# Puzzle_Controller.net
KiCad netlist of a schematic drawn in EAGLE
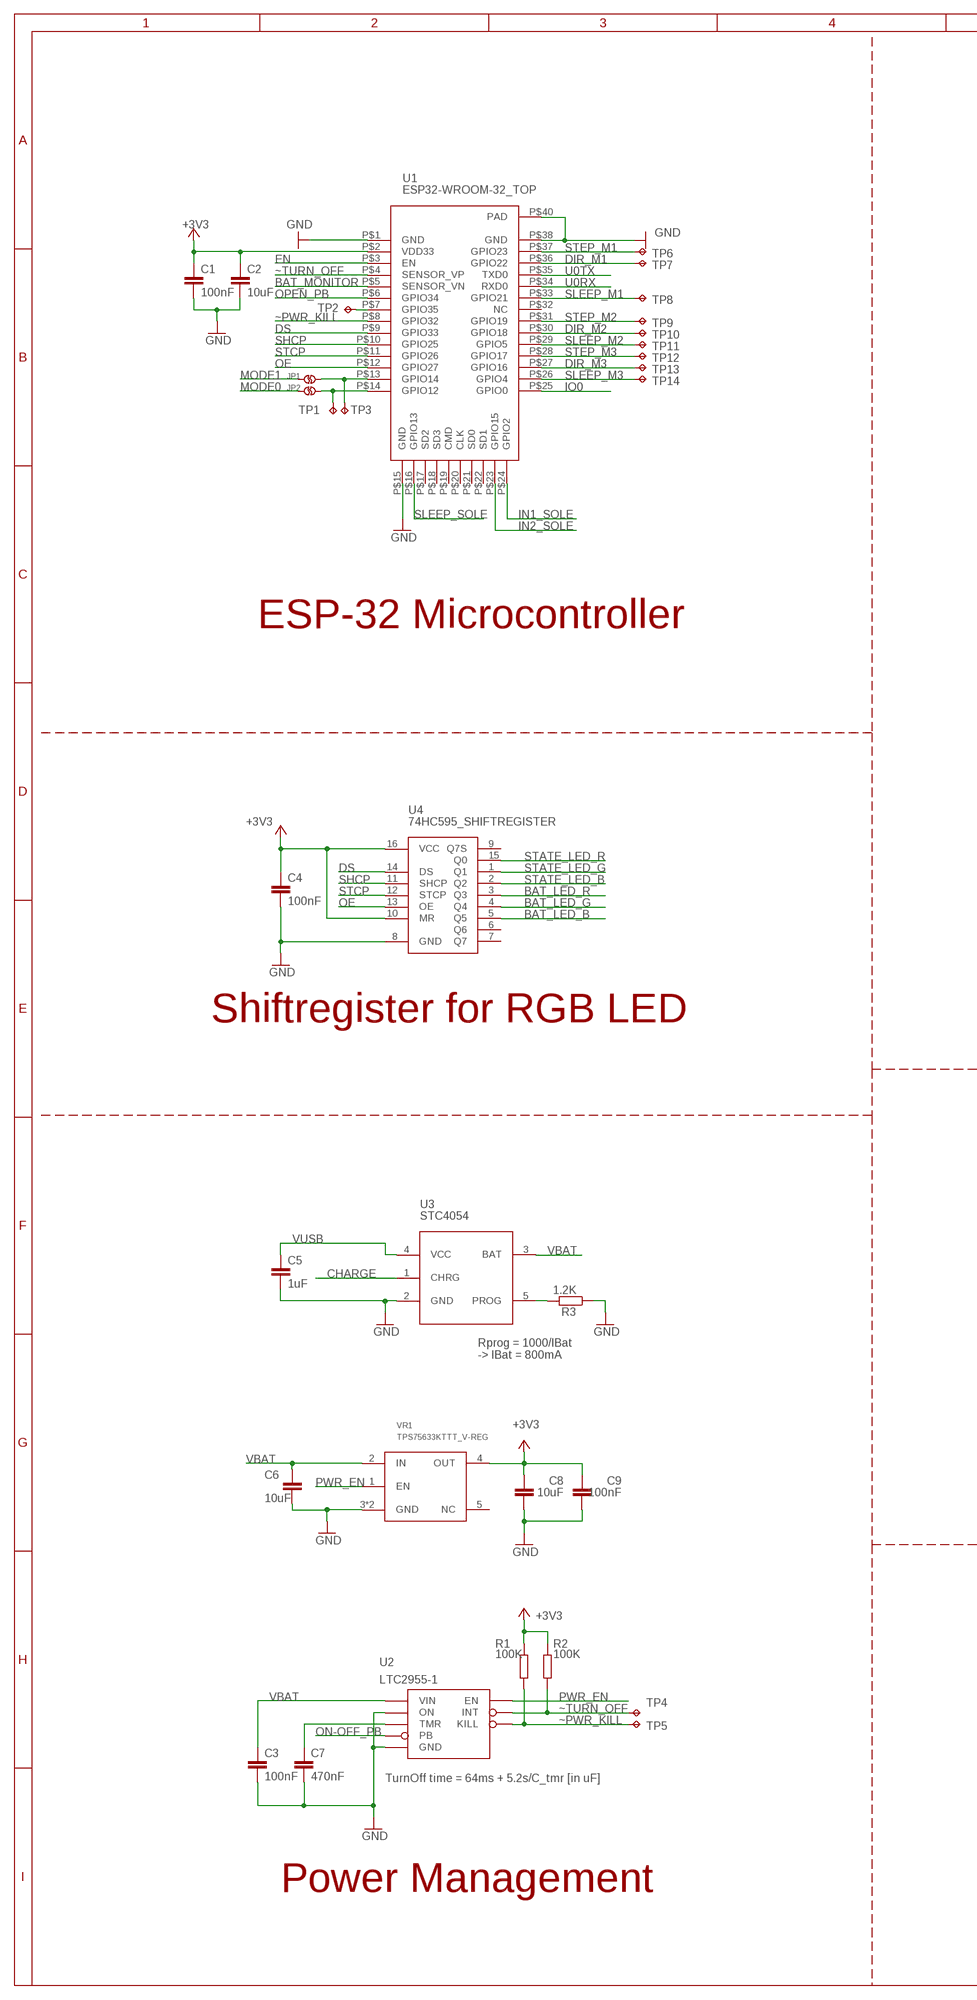
[diagram p0: schematic, sheet 1, part 1 of 2]
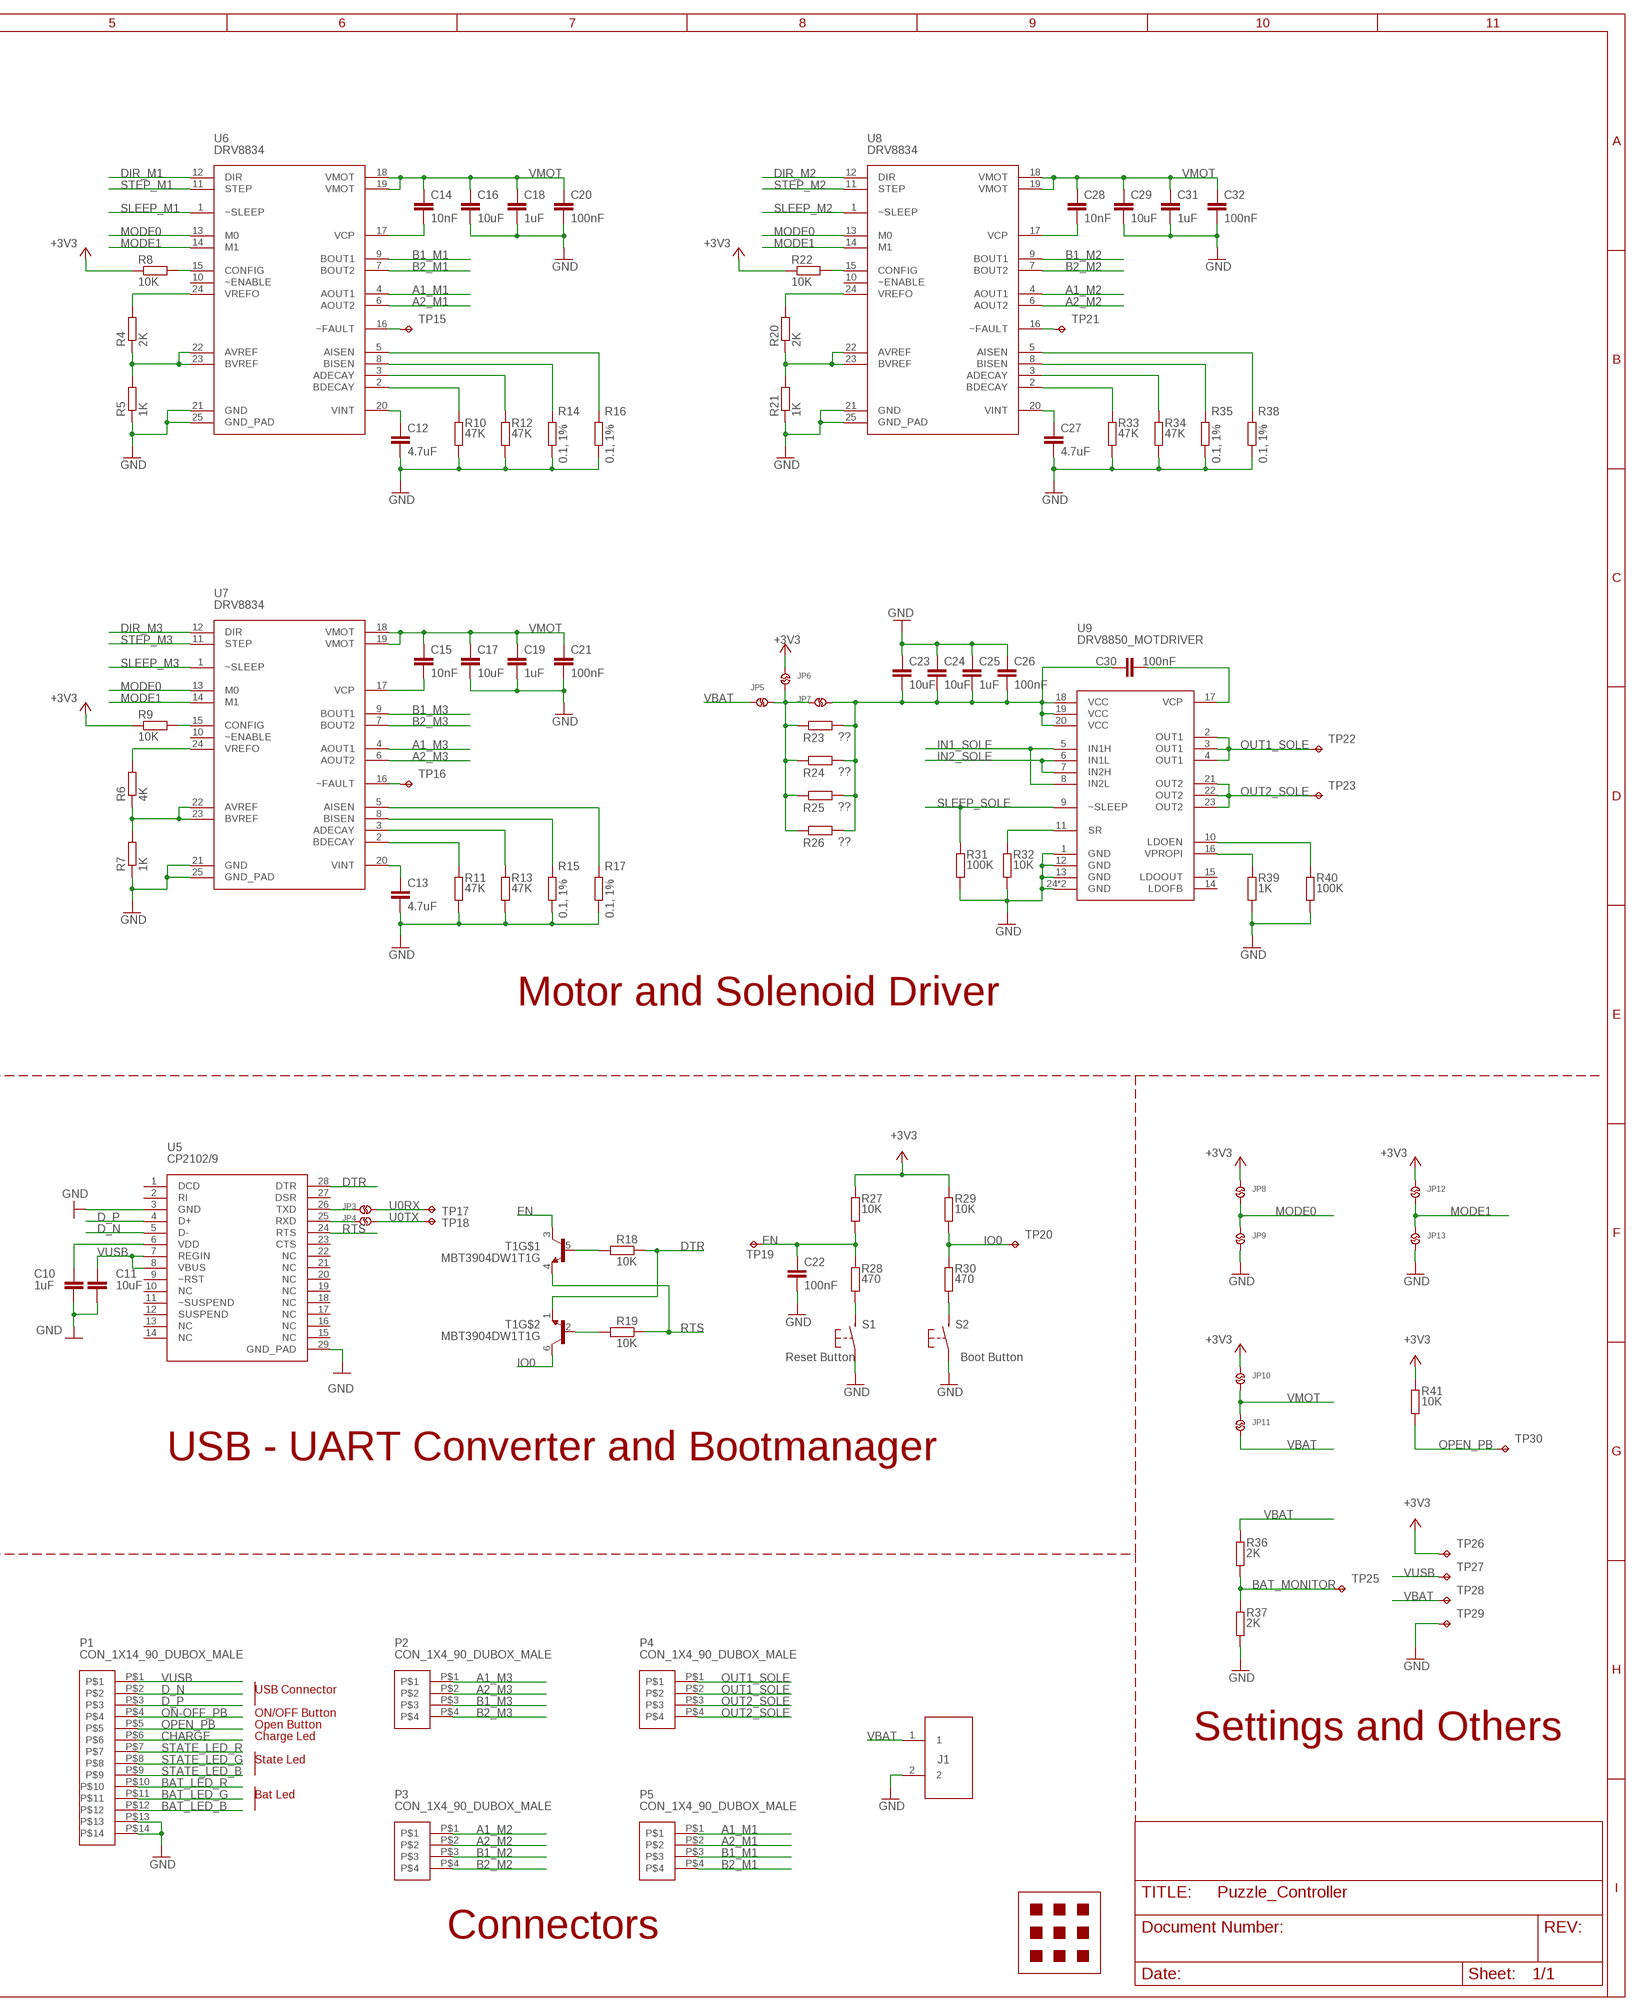
[diagram p1: schematic, sheet 1, part 2 of 2]

(export (version "E")
  (design (tool "Eeschema 10.0.6"))
  (components
    (comp (ref "C1")
      (value "100nF")
      (footprint "eagle-import:0603")
      (libsource (lib "eagle-import") (part "CAP_0603"))
    )
    (comp (ref "C2")
      (value "10uF")
      (footprint "eagle-import:0603")
      (libsource (lib "eagle-import") (part "CAP_0603"))
    )
    (comp (ref "C3")
      (value "100nF")
      (footprint "eagle-import:0603")
      (libsource (lib "eagle-import") (part "CAP_0603"))
    )
    (comp (ref "C4")
      (value "100nF")
      (footprint "eagle-import:0603")
      (libsource (lib "eagle-import") (part "CAP_0603"))
    )
    (comp (ref "C5")
      (value "1uF")
      (footprint "eagle-import:0603")
      (libsource (lib "eagle-import") (part "CAP_0603"))
    )
    (comp (ref "C6")
      (value "10uF")
      (footprint "eagle-import:0603")
      (libsource (lib "eagle-import") (part "CAP_0603"))
    )
    (comp (ref "C7")
      (value "470nF")
      (footprint "eagle-import:0603")
      (libsource (lib "eagle-import") (part "CAP_0603"))
    )
    (comp (ref "C8")
      (value "10uF")
      (footprint "eagle-import:0603")
      (libsource (lib "eagle-import") (part "CAP_0603"))
    )
    (comp (ref "C9")
      (value "100nF")
      (footprint "eagle-import:0603")
      (libsource (lib "eagle-import") (part "CAP_0603"))
    )
    (comp (ref "C10")
      (value "1uF")
      (footprint "eagle-import:0603")
      (libsource (lib "eagle-import") (part "CAP_0603"))
    )
    (comp (ref "C11")
      (value "10uF")
      (footprint "eagle-import:0603")
      (libsource (lib "eagle-import") (part "CAP_0603"))
    )
    (comp (ref "C12")
      (value "4.7uF")
      (footprint "eagle-import:0603")
      (libsource (lib "eagle-import") (part "CAP_0603"))
    )
    (comp (ref "C13")
      (value "4.7uF")
      (footprint "eagle-import:0603")
      (libsource (lib "eagle-import") (part "CAP_0603"))
    )
    (comp (ref "C14")
      (value "10nF")
      (footprint "eagle-import:0603")
      (libsource (lib "eagle-import") (part "CAP_0603"))
    )
    (comp (ref "C15")
      (value "10nF")
      (footprint "eagle-import:0603")
      (libsource (lib "eagle-import") (part "CAP_0603"))
    )
    (comp (ref "C16")
      (value "10uF")
      (footprint "eagle-import:0603")
      (libsource (lib "eagle-import") (part "CAP_0603"))
    )
    (comp (ref "C17")
      (value "10uF")
      (footprint "eagle-import:0603")
      (libsource (lib "eagle-import") (part "CAP_0603"))
    )
    (comp (ref "C18")
      (value "1uF")
      (footprint "eagle-import:0603")
      (libsource (lib "eagle-import") (part "CAP_0603"))
    )
    (comp (ref "C19")
      (value "1uF")
      (footprint "eagle-import:0603")
      (libsource (lib "eagle-import") (part "CAP_0603"))
    )
    (comp (ref "C20")
      (value "100nF")
      (footprint "eagle-import:0603")
      (libsource (lib "eagle-import") (part "CAP_0603"))
    )
    (comp (ref "C21")
      (value "100nF")
      (footprint "eagle-import:0603")
      (libsource (lib "eagle-import") (part "CAP_0603"))
    )
    (comp (ref "C22")
      (value "100nF")
      (footprint "eagle-import:0603")
      (libsource (lib "eagle-import") (part "CAP_0603"))
    )
    (comp (ref "C23")
      (value "10uF")
      (footprint "eagle-import:0603")
      (libsource (lib "eagle-import") (part "CAP_0603"))
    )
    (comp (ref "C24")
      (value "10uF")
      (footprint "eagle-import:0603")
      (libsource (lib "eagle-import") (part "CAP_0603"))
    )
    (comp (ref "C25")
      (value "1uF")
      (footprint "eagle-import:0603")
      (libsource (lib "eagle-import") (part "CAP_0603"))
    )
    (comp (ref "C26")
      (value "100nF")
      (footprint "eagle-import:0603")
      (libsource (lib "eagle-import") (part "CAP_0603"))
    )
    (comp (ref "C27")
      (value "4.7uF")
      (footprint "eagle-import:0603")
      (libsource (lib "eagle-import") (part "CAP_0603"))
    )
    (comp (ref "C28")
      (value "10nF")
      (footprint "eagle-import:0603")
      (libsource (lib "eagle-import") (part "CAP_0603"))
    )
    (comp (ref "C29")
      (value "10uF")
      (footprint "eagle-import:0603")
      (libsource (lib "eagle-import") (part "CAP_0603"))
    )
    (comp (ref "C30")
      (value "100nF")
      (footprint "eagle-import:0603")
      (libsource (lib "eagle-import") (part "CAP_0603"))
    )
    (comp (ref "C31")
      (value "1uF")
      (footprint "eagle-import:0603")
      (libsource (lib "eagle-import") (part "CAP_0603"))
    )
    (comp (ref "C32")
      (value "100nF")
      (footprint "eagle-import:0603")
      (libsource (lib "eagle-import") (part "CAP_0603"))
    )
    (comp (ref "J1")
      (value "CON_2")
      (footprint "eagle-import:CON_2")
      (libsource (lib "eagle-import") (part "CON_2"))
    )
    (comp (ref "JP1")
      (value "SOLDER_JUMPER")
      (footprint "eagle-import:SOLDER_JUMPER")
      (libsource (lib "eagle-import") (part "SOLDER_JUMPER"))
    )
    (comp (ref "JP2")
      (value "SOLDER_JUMPER")
      (footprint "eagle-import:SOLDER_JUMPER")
      (libsource (lib "eagle-import") (part "SOLDER_JUMPER"))
    )
    (comp (ref "JP3")
      (value "SOLDER_JUMPER")
      (footprint "eagle-import:SOLDER_JUMPER")
      (libsource (lib "eagle-import") (part "SOLDER_JUMPER"))
    )
    (comp (ref "JP4")
      (value "SOLDER_JUMPER")
      (footprint "eagle-import:SOLDER_JUMPER")
      (libsource (lib "eagle-import") (part "SOLDER_JUMPER"))
    )
    (comp (ref "JP5")
      (value "SOLDER_JUMPER")
      (footprint "eagle-import:SOLDER_JUMPER")
      (libsource (lib "eagle-import") (part "SOLDER_JUMPER"))
    )
    (comp (ref "JP6")
      (value "SOLDER_JUMPER")
      (footprint "eagle-import:SOLDER_JUMPER")
      (libsource (lib "eagle-import") (part "SOLDER_JUMPER"))
    )
    (comp (ref "JP7")
      (value "SOLDER_JUMPER")
      (footprint "eagle-import:SOLDER_JUMPER")
      (libsource (lib "eagle-import") (part "SOLDER_JUMPER"))
    )
    (comp (ref "JP8")
      (value "SOLDER_JUMPER")
      (footprint "eagle-import:SOLDER_JUMPER")
      (libsource (lib "eagle-import") (part "SOLDER_JUMPER"))
    )
    (comp (ref "JP9")
      (value "SOLDER_JUMPER")
      (footprint "eagle-import:SOLDER_JUMPER")
      (libsource (lib "eagle-import") (part "SOLDER_JUMPER"))
    )
    (comp (ref "JP10")
      (value "SOLDER_JUMPER")
      (footprint "eagle-import:SOLDER_JUMPER")
      (libsource (lib "eagle-import") (part "SOLDER_JUMPER"))
    )
    (comp (ref "JP11")
      (value "SOLDER_JUMPER")
      (footprint "eagle-import:SOLDER_JUMPER")
      (libsource (lib "eagle-import") (part "SOLDER_JUMPER"))
    )
    (comp (ref "JP12")
      (value "SOLDER_JUMPER")
      (footprint "eagle-import:SOLDER_JUMPER")
      (libsource (lib "eagle-import") (part "SOLDER_JUMPER"))
    )
    (comp (ref "JP13")
      (value "SOLDER_JUMPER")
      (footprint "eagle-import:SOLDER_JUMPER")
      (libsource (lib "eagle-import") (part "SOLDER_JUMPER"))
    )
    (comp (ref "MEC1")
      (value "FREESTYLE_PAD")
      (footprint "eagle-import:FREESTYLE_PAD")
      (libsource (lib "eagle-import") (part "FREESTYLE_PAD"))
    )
    (comp (ref "P1")
      (value "CON_1X14_90_DUBOX_MALE")
      (footprint "eagle-import:CON_1X14_90_DUBOX_MALE")
      (libsource (lib "eagle-import") (part "CON_1X14_90_DUBOX_MALE"))
    )
    (comp (ref "P2")
      (value "CON_1X4_90_DUBOX_MALE")
      (footprint "eagle-import:CON_1X4_90_DUBOX_MALE")
      (libsource (lib "eagle-import") (part "CON_1X4_90_DUBOX_MALE"))
    )
    (comp (ref "P3")
      (value "CON_1X4_90_DUBOX_MALE")
      (footprint "eagle-import:CON_1X4_90_DUBOX_MALE")
      (libsource (lib "eagle-import") (part "CON_1X4_90_DUBOX_MALE"))
    )
    (comp (ref "P4")
      (value "CON_1X4_90_DUBOX_MALE")
      (footprint "eagle-import:CON_1X4_90_DUBOX_MALE")
      (libsource (lib "eagle-import") (part "CON_1X4_90_DUBOX_MALE"))
    )
    (comp (ref "P5")
      (value "CON_1X4_90_DUBOX_MALE")
      (footprint "eagle-import:CON_1X4_90_DUBOX_MALE")
      (libsource (lib "eagle-import") (part "CON_1X4_90_DUBOX_MALE"))
    )
    (comp (ref "R1")
      (value "100K")
      (footprint "eagle-import:0603")
      (libsource (lib "eagle-import") (part "RES_0603"))
    )
    (comp (ref "R2")
      (value "100K")
      (footprint "eagle-import:0603")
      (libsource (lib "eagle-import") (part "RES_0603"))
    )
    (comp (ref "R3")
      (value "1.2K")
      (footprint "eagle-import:0603")
      (libsource (lib "eagle-import") (part "RES_0603"))
    )
    (comp (ref "R4")
      (value "2K")
      (footprint "eagle-import:0603")
      (libsource (lib "eagle-import") (part "RES_0603"))
    )
    (comp (ref "R5")
      (value "1K")
      (footprint "eagle-import:0603")
      (libsource (lib "eagle-import") (part "RES_0603"))
    )
    (comp (ref "R6")
      (value "4K")
      (footprint "eagle-import:0603")
      (libsource (lib "eagle-import") (part "RES_0603"))
    )
    (comp (ref "R7")
      (value "1K")
      (footprint "eagle-import:0603")
      (libsource (lib "eagle-import") (part "RES_0603"))
    )
    (comp (ref "R8")
      (value "10K")
      (footprint "eagle-import:0603")
      (libsource (lib "eagle-import") (part "RES_0603"))
    )
    (comp (ref "R9")
      (value "10K")
      (footprint "eagle-import:0603")
      (libsource (lib "eagle-import") (part "RES_0603"))
    )
    (comp (ref "R10")
      (value "47K")
      (footprint "eagle-import:0603")
      (libsource (lib "eagle-import") (part "RES_0603"))
    )
    (comp (ref "R11")
      (value "47K")
      (footprint "eagle-import:0603")
      (libsource (lib "eagle-import") (part "RES_0603"))
    )
    (comp (ref "R12")
      (value "47K")
      (footprint "eagle-import:0603")
      (libsource (lib "eagle-import") (part "RES_0603"))
    )
    (comp (ref "R13")
      (value "47K")
      (footprint "eagle-import:0603")
      (libsource (lib "eagle-import") (part "RES_0603"))
    )
    (comp (ref "R14")
      (value "0.1, 1%")
      (footprint "eagle-import:0603")
      (libsource (lib "eagle-import") (part "RES_0603"))
    )
    (comp (ref "R15")
      (value "0.1, 1%")
      (footprint "eagle-import:0603")
      (libsource (lib "eagle-import") (part "RES_0603"))
    )
    (comp (ref "R16")
      (value "0.1, 1%")
      (footprint "eagle-import:0603")
      (libsource (lib "eagle-import") (part "RES_0603"))
    )
    (comp (ref "R17")
      (value "0.1, 1%")
      (footprint "eagle-import:0603")
      (libsource (lib "eagle-import") (part "RES_0603"))
    )
    (comp (ref "R18")
      (value "10K")
      (footprint "eagle-import:0603")
      (libsource (lib "eagle-import") (part "RES_0603"))
    )
    (comp (ref "R19")
      (value "10K")
      (footprint "eagle-import:0603")
      (libsource (lib "eagle-import") (part "RES_0603"))
    )
    (comp (ref "R20")
      (value "2K")
      (footprint "eagle-import:0603")
      (libsource (lib "eagle-import") (part "RES_0603"))
    )
    (comp (ref "R21")
      (value "1K")
      (footprint "eagle-import:0603")
      (libsource (lib "eagle-import") (part "RES_0603"))
    )
    (comp (ref "R22")
      (value "10K")
      (footprint "eagle-import:0603")
      (libsource (lib "eagle-import") (part "RES_0603"))
    )
    (comp (ref "R23")
      (value "??")
      (footprint "eagle-import:0603")
      (libsource (lib "eagle-import") (part "RES_0603"))
    )
    (comp (ref "R24")
      (value "??")
      (footprint "eagle-import:0603")
      (libsource (lib "eagle-import") (part "RES_0603"))
    )
    (comp (ref "R25")
      (value "??")
      (footprint "eagle-import:0603")
      (libsource (lib "eagle-import") (part "RES_0603"))
    )
    (comp (ref "R26")
      (value "??")
      (footprint "eagle-import:0603")
      (libsource (lib "eagle-import") (part "RES_0603"))
    )
    (comp (ref "R27")
      (value "10K")
      (footprint "eagle-import:0603")
      (libsource (lib "eagle-import") (part "RES_0603"))
    )
    (comp (ref "R28")
      (value "470")
      (footprint "eagle-import:0603")
      (libsource (lib "eagle-import") (part "RES_0603"))
    )
    (comp (ref "R29")
      (value "10K")
      (footprint "eagle-import:0603")
      (libsource (lib "eagle-import") (part "RES_0603"))
    )
    (comp (ref "R30")
      (value "470")
      (footprint "eagle-import:0603")
      (libsource (lib "eagle-import") (part "RES_0603"))
    )
    (comp (ref "R31")
      (value "100K")
      (footprint "eagle-import:0603")
      (libsource (lib "eagle-import") (part "RES_0603"))
    )
    (comp (ref "R32")
      (value "10K")
      (footprint "eagle-import:0603")
      (libsource (lib "eagle-import") (part "RES_0603"))
    )
    (comp (ref "R33")
      (value "47K")
      (footprint "eagle-import:0603")
      (libsource (lib "eagle-import") (part "RES_0603"))
    )
    (comp (ref "R34")
      (value "47K")
      (footprint "eagle-import:0603")
      (libsource (lib "eagle-import") (part "RES_0603"))
    )
    (comp (ref "R35")
      (value "0.1, 1%")
      (footprint "eagle-import:0603")
      (libsource (lib "eagle-import") (part "RES_0603"))
    )
    (comp (ref "R36")
      (value "2K")
      (footprint "eagle-import:0603")
      (libsource (lib "eagle-import") (part "RES_0603"))
    )
    (comp (ref "R37")
      (value "2K")
      (footprint "eagle-import:0603")
      (libsource (lib "eagle-import") (part "RES_0603"))
    )
    (comp (ref "R38")
      (value "0.1, 1%")
      (footprint "eagle-import:0603")
      (libsource (lib "eagle-import") (part "RES_0603"))
    )
    (comp (ref "R39")
      (value "1K")
      (footprint "eagle-import:0603")
      (libsource (lib "eagle-import") (part "RES_0603"))
    )
    (comp (ref "R40")
      (value "100K")
      (footprint "eagle-import:0603")
      (libsource (lib "eagle-import") (part "RES_0603"))
    )
    (comp (ref "R41")
      (value "10K")
      (footprint "eagle-import:0603")
      (libsource (lib "eagle-import") (part "RES_0603"))
    )
    (comp (ref "S1")
      (value "B3U-1000P")
      (footprint "eagle-import:B3U-1000P")
      (libsource (lib "eagle-import") (part "BUTTON_B3U-1000P"))
    )
    (comp (ref "S2")
      (value "B3U-1000P")
      (footprint "eagle-import:B3U-1000P")
      (libsource (lib "eagle-import") (part "BUTTON_B3U-1000P"))
    )
    (comp (ref "T1")
      (value "MBT3904DW1T1G")
      (footprint "eagle-import:SOT23-6")
      (libsource (lib "eagle-import") (part "MBT3904DW1T1G"))
    )
    (comp (ref "TP1")
      (value "TP")
      (footprint "eagle-import:TEST_PAD")
      (libsource (lib "eagle-import") (part "TP"))
    )
    (comp (ref "TP2")
      (value "TP")
      (footprint "eagle-import:TEST_PAD")
      (libsource (lib "eagle-import") (part "TP"))
    )
    (comp (ref "TP3")
      (value "TP")
      (footprint "eagle-import:TEST_PAD")
      (libsource (lib "eagle-import") (part "TP"))
    )
    (comp (ref "TP4")
      (value "TP")
      (footprint "eagle-import:TEST_PAD")
      (libsource (lib "eagle-import") (part "TP"))
    )
    (comp (ref "TP5")
      (value "TP")
      (footprint "eagle-import:TEST_PAD")
      (libsource (lib "eagle-import") (part "TP"))
    )
    (comp (ref "TP6")
      (value "TP")
      (footprint "eagle-import:TEST_PAD")
      (libsource (lib "eagle-import") (part "TP"))
    )
    (comp (ref "TP7")
      (value "TP")
      (footprint "eagle-import:TEST_PAD")
      (libsource (lib "eagle-import") (part "TP"))
    )
    (comp (ref "TP8")
      (value "TP")
      (footprint "eagle-import:TEST_PAD")
      (libsource (lib "eagle-import") (part "TP"))
    )
    (comp (ref "TP9")
      (value "TP")
      (footprint "eagle-import:TEST_PAD")
      (libsource (lib "eagle-import") (part "TP"))
    )
    (comp (ref "TP10")
      (value "TP")
      (footprint "eagle-import:TEST_PAD")
      (libsource (lib "eagle-import") (part "TP"))
    )
    (comp (ref "TP11")
      (value "TP")
      (footprint "eagle-import:TEST_PAD")
      (libsource (lib "eagle-import") (part "TP"))
    )
    (comp (ref "TP12")
      (value "TP")
      (footprint "eagle-import:TEST_PAD")
      (libsource (lib "eagle-import") (part "TP"))
    )
    (comp (ref "TP13")
      (value "TP")
      (footprint "eagle-import:TEST_PAD")
      (libsource (lib "eagle-import") (part "TP"))
    )
    (comp (ref "TP14")
      (value "TP")
      (footprint "eagle-import:TEST_PAD")
      (libsource (lib "eagle-import") (part "TP"))
    )
    (comp (ref "TP15")
      (value "TP")
      (footprint "eagle-import:TEST_PAD")
      (libsource (lib "eagle-import") (part "TP"))
    )
    (comp (ref "TP16")
      (value "TP")
      (footprint "eagle-import:TEST_PAD")
      (libsource (lib "eagle-import") (part "TP"))
    )
    (comp (ref "TP17")
      (value "TP")
      (footprint "eagle-import:TEST_PAD")
      (libsource (lib "eagle-import") (part "TP"))
    )
    (comp (ref "TP18")
      (value "TP")
      (footprint "eagle-import:TEST_PAD")
      (libsource (lib "eagle-import") (part "TP"))
    )
    (comp (ref "TP19")
      (value "TP")
      (footprint "eagle-import:TEST_PAD")
      (libsource (lib "eagle-import") (part "TP"))
    )
    (comp (ref "TP20")
      (value "TP")
      (footprint "eagle-import:TEST_PAD")
      (libsource (lib "eagle-import") (part "TP"))
    )
    (comp (ref "TP21")
      (value "TP")
      (footprint "eagle-import:TEST_PAD")
      (libsource (lib "eagle-import") (part "TP"))
    )
    (comp (ref "TP22")
      (value "TP")
      (footprint "eagle-import:TEST_PAD")
      (libsource (lib "eagle-import") (part "TP"))
    )
    (comp (ref "TP23")
      (value "TP")
      (footprint "eagle-import:TEST_PAD")
      (libsource (lib "eagle-import") (part "TP"))
    )
    (comp (ref "TP25")
      (value "TP")
      (footprint "eagle-import:TEST_PAD")
      (libsource (lib "eagle-import") (part "TP"))
    )
    (comp (ref "TP26")
      (value "TP")
      (footprint "eagle-import:TEST_PAD")
      (libsource (lib "eagle-import") (part "TP"))
    )
    (comp (ref "TP27")
      (value "TP")
      (footprint "eagle-import:TEST_PAD")
      (libsource (lib "eagle-import") (part "TP"))
    )
    (comp (ref "TP28")
      (value "TP")
      (footprint "eagle-import:TEST_PAD")
      (libsource (lib "eagle-import") (part "TP"))
    )
    (comp (ref "TP29")
      (value "TP")
      (footprint "eagle-import:TEST_PAD")
      (libsource (lib "eagle-import") (part "TP"))
    )
    (comp (ref "TP30")
      (value "TP")
      (footprint "eagle-import:TEST_PAD")
      (libsource (lib "eagle-import") (part "TP"))
    )
    (comp (ref "U1")
      (value "ESP32-WROOM-32_TOP")
      (footprint "eagle-import:ESP32-WROOM-32_TOP")
      (libsource (lib "eagle-import") (part "ESP32-WROOM-32_TOP"))
    )
    (comp (ref "U2")
      (value "LTC2955-1")
      (footprint "eagle-import:SOT23-8")
      (libsource (lib "eagle-import") (part "LTC2955-1_ON/OFF_CTLR"))
    )
    (comp (ref "U3")
      (value "STC4054")
      (footprint "eagle-import:TSOT23-5L")
      (libsource (lib "eagle-import") (part "STC4054_BAT_CHARGER"))
    )
    (comp (ref "U4")
      (value "74HC595_SHIFTREGISTER")
      (footprint "eagle-import:SOIC-16")
      (libsource (lib "eagle-import") (part "74HC595_SHIFTREGISTER"))
    )
    (comp (ref "U5")
      (value "CP2102/9")
      (footprint "eagle-import:QFN-28")
      (libsource (lib "eagle-import") (part "CP2102/9"))
    )
    (comp (ref "U6")
      (value "DRV8834")
      (footprint "eagle-import:TSSOP-24")
      (libsource (lib "eagle-import") (part "DRV8834"))
    )
    (comp (ref "U7")
      (value "DRV8834")
      (footprint "eagle-import:TSSOP-24")
      (libsource (lib "eagle-import") (part "DRV8834"))
    )
    (comp (ref "U8")
      (value "DRV8834")
      (footprint "eagle-import:TSSOP-24")
      (libsource (lib "eagle-import") (part "DRV8834"))
    )
    (comp (ref "U9")
      (value "DRV8850_MOTDRIVER")
      (footprint "eagle-import:QFN-24")
      (libsource (lib "eagle-import") (part "DRV8850_MOTDRIVER"))
    )
    (comp (ref "VR1")
      (value "TPS75633KTTT_V-REG")
      (footprint "eagle-import:TPS75633KTTT_V-REG")
      (libsource (lib "eagle-import") (part "TPS75633KTTT_V-REG"))
    )
  )
  (nets
    (net (code "1") (name "+3V3") (class "Default")
      (node (ref "C1") (pin "1") (pinfunction "1_1") (pintype "passive"))
      (node (ref "C2") (pin "1") (pinfunction "1_1") (pintype "passive"))
      (node (ref "C4") (pin "1") (pinfunction "1_1") (pintype "passive"))
      (node (ref "C8") (pin "2") (pinfunction "2_2") (pintype "passive"))
      (node (ref "C9") (pin "2") (pinfunction "2_2") (pintype "passive"))
      (node (ref "JP10") (pin "P$1") (pinfunction "P$1_P$1") (pintype "bidirectional"))
      (node (ref "JP12") (pin "P$1") (pinfunction "P$1_P$1") (pintype "bidirectional"))
      (node (ref "JP6") (pin "P$2") (pinfunction "P$2_P$2") (pintype "bidirectional"))
      (node (ref "JP8") (pin "P$1") (pinfunction "P$1_P$1") (pintype "bidirectional"))
      (node (ref "R1") (pin "1") (pinfunction "1_1") (pintype "passive"))
      (node (ref "R2") (pin "1") (pinfunction "1_1") (pintype "passive"))
      (node (ref "R22") (pin "1") (pinfunction "1_1") (pintype "passive"))
      (node (ref "R27") (pin "2") (pinfunction "2_2") (pintype "passive"))
      (node (ref "R29") (pin "2") (pinfunction "2_2") (pintype "passive"))
      (node (ref "R41") (pin "2") (pinfunction "2_2") (pintype "passive"))
      (node (ref "R8") (pin "1") (pinfunction "1_1") (pintype "passive"))
      (node (ref "R9") (pin "1") (pinfunction "1_1") (pintype "passive"))
      (node (ref "TP26") (pin "TP") (pinfunction "TP_TP") (pintype "input"))
      (node (ref "U1") (pin "P$2") (pinfunction "VDD33_P$2") (pintype "bidirectional"))
      (node (ref "U4") (pin "10") (pinfunction "MR_10") (pintype "bidirectional"))
      (node (ref "U4") (pin "16") (pinfunction "VCC_16") (pintype "bidirectional"))
      (node (ref "VR1") (pin "4") (pinfunction "OUT_4") (pintype "bidirectional"))
    )
    (net (code "2") (name "/A1_M1") (class "Default")
      (node (ref "P5") (pin "P$1") (pinfunction "P$1_P$1") (pintype "bidirectional"))
      (node (ref "U6") (pin "4") (pinfunction "AOUT1_4") (pintype "bidirectional"))
    )
    (net (code "3") (name "/A1_M2") (class "Default")
      (node (ref "P3") (pin "P$1") (pinfunction "P$1_P$1") (pintype "bidirectional"))
      (node (ref "U8") (pin "4") (pinfunction "AOUT1_4") (pintype "bidirectional"))
    )
    (net (code "4") (name "/A1_M3") (class "Default")
      (node (ref "P2") (pin "P$1") (pinfunction "P$1_P$1") (pintype "bidirectional"))
      (node (ref "U7") (pin "4") (pinfunction "AOUT1_4") (pintype "bidirectional"))
    )
    (net (code "5") (name "/A2_M1") (class "Default")
      (node (ref "P5") (pin "P$2") (pinfunction "P$2_P$2") (pintype "bidirectional"))
      (node (ref "U6") (pin "6") (pinfunction "AOUT2_6") (pintype "bidirectional"))
    )
    (net (code "6") (name "/A2_M2") (class "Default")
      (node (ref "P3") (pin "P$2") (pinfunction "P$2_P$2") (pintype "bidirectional"))
      (node (ref "U8") (pin "6") (pinfunction "AOUT2_6") (pintype "bidirectional"))
    )
    (net (code "7") (name "/A2_M3") (class "Default")
      (node (ref "P2") (pin "P$2") (pinfunction "P$2_P$2") (pintype "bidirectional"))
      (node (ref "U7") (pin "6") (pinfunction "AOUT2_6") (pintype "bidirectional"))
    )
    (net (code "8") (name "/B1_M1") (class "Default")
      (node (ref "P5") (pin "P$3") (pinfunction "P$3_P$3") (pintype "bidirectional"))
      (node (ref "U6") (pin "9") (pinfunction "BOUT1_9") (pintype "bidirectional"))
    )
    (net (code "9") (name "/B1_M2") (class "Default")
      (node (ref "P3") (pin "P$3") (pinfunction "P$3_P$3") (pintype "bidirectional"))
      (node (ref "U8") (pin "9") (pinfunction "BOUT1_9") (pintype "bidirectional"))
    )
    (net (code "10") (name "/B1_M3") (class "Default")
      (node (ref "P2") (pin "P$3") (pinfunction "P$3_P$3") (pintype "bidirectional"))
      (node (ref "U7") (pin "9") (pinfunction "BOUT1_9") (pintype "bidirectional"))
    )
    (net (code "11") (name "/B2_M1") (class "Default")
      (node (ref "P5") (pin "P$4") (pinfunction "P$4_P$4") (pintype "bidirectional"))
      (node (ref "U6") (pin "7") (pinfunction "BOUT2_7") (pintype "bidirectional"))
    )
    (net (code "12") (name "/B2_M2") (class "Default")
      (node (ref "P3") (pin "P$4") (pinfunction "P$4_P$4") (pintype "bidirectional"))
      (node (ref "U8") (pin "7") (pinfunction "BOUT2_7") (pintype "bidirectional"))
    )
    (net (code "13") (name "/B2_M3") (class "Default")
      (node (ref "P2") (pin "P$4") (pinfunction "P$4_P$4") (pintype "bidirectional"))
      (node (ref "U7") (pin "7") (pinfunction "BOUT2_7") (pintype "bidirectional"))
    )
    (net (code "14") (name "/BAT_LED_B") (class "Default")
      (node (ref "P1") (pin "P$12") (pinfunction "P$12_P$12") (pintype "bidirectional"))
      (node (ref "U4") (pin "5") (pinfunction "Q5_5") (pintype "bidirectional"))
    )
    (net (code "15") (name "/BAT_LED_G") (class "Default")
      (node (ref "P1") (pin "P$11") (pinfunction "P$11_P$11") (pintype "bidirectional"))
      (node (ref "U4") (pin "4") (pinfunction "Q4_4") (pintype "bidirectional"))
    )
    (net (code "16") (name "/BAT_LED_R") (class "Default")
      (node (ref "P1") (pin "P$10") (pinfunction "P$10_P$10") (pintype "bidirectional"))
      (node (ref "U4") (pin "3") (pinfunction "Q3_3") (pintype "bidirectional"))
    )
    (net (code "17") (name "/BAT_MONITOR") (class "Default")
      (node (ref "R36") (pin "2") (pinfunction "2_2") (pintype "passive"))
      (node (ref "R37") (pin "1") (pinfunction "1_1") (pintype "passive"))
      (node (ref "TP25") (pin "TP") (pinfunction "TP_TP") (pintype "input"))
      (node (ref "U1") (pin "P$5") (pinfunction "SENSOR_VN_P$5") (pintype "bidirectional"))
    )
    (net (code "18") (name "/CHARGE") (class "Default")
      (node (ref "P1") (pin "P$6") (pinfunction "P$6_P$6") (pintype "bidirectional"))
      (node (ref "U3") (pin "1") (pinfunction "CHRG_1") (pintype "bidirectional"))
    )
    (net (code "19") (name "/DIR_M1") (class "Default")
      (node (ref "TP7") (pin "TP") (pinfunction "TP_TP") (pintype "input"))
      (node (ref "U1") (pin "P$36") (pinfunction "GPIO22_P$36") (pintype "bidirectional"))
      (node (ref "U6") (pin "12") (pinfunction "DIR_12") (pintype "bidirectional"))
    )
    (net (code "20") (name "/DIR_M2") (class "Default")
      (node (ref "TP10") (pin "TP") (pinfunction "TP_TP") (pintype "input"))
      (node (ref "U1") (pin "P$30") (pinfunction "GPIO18_P$30") (pintype "bidirectional"))
      (node (ref "U8") (pin "12") (pinfunction "DIR_12") (pintype "bidirectional"))
    )
    (net (code "21") (name "/DIR_M3") (class "Default")
      (node (ref "TP13") (pin "TP") (pinfunction "TP_TP") (pintype "input"))
      (node (ref "U1") (pin "P$27") (pinfunction "GPIO16_P$27") (pintype "bidirectional"))
      (node (ref "U7") (pin "12") (pinfunction "DIR_12") (pintype "bidirectional"))
    )
    (net (code "22") (name "/DS") (class "Default")
      (node (ref "U1") (pin "P$9") (pinfunction "GPIO33_P$9") (pintype "bidirectional"))
      (node (ref "U4") (pin "14") (pinfunction "DS_14") (pintype "bidirectional"))
    )
    (net (code "23") (name "/DTR") (class "Default")
      (node (ref "R18") (pin "1") (pinfunction "1_1") (pintype "passive"))
      (node (ref "T1") (pin "1") (pinfunction "E_1") (pintype "passive"))
      (node (ref "U5") (pin "28") (pinfunction "DTR_28") (pintype "bidirectional"))
    )
    (net (code "24") (name "/D_N") (class "Default")
      (node (ref "P1") (pin "P$2") (pinfunction "P$2_P$2") (pintype "bidirectional"))
      (node (ref "U5") (pin "5") (pinfunction "D-_5") (pintype "bidirectional"))
    )
    (net (code "25") (name "/D_P") (class "Default")
      (node (ref "P1") (pin "P$3") (pinfunction "P$3_P$3") (pintype "bidirectional"))
      (node (ref "U5") (pin "4") (pinfunction "D+_4") (pintype "bidirectional"))
    )
    (net (code "26") (name "/EN") (class "Default")
      (node (ref "C22") (pin "1") (pinfunction "1_1") (pintype "passive"))
      (node (ref "R27") (pin "1") (pinfunction "1_1") (pintype "passive"))
      (node (ref "R28") (pin "2") (pinfunction "2_2") (pintype "passive"))
      (node (ref "T1") (pin "3") (pinfunction "C_3") (pintype "passive"))
      (node (ref "TP19") (pin "TP") (pinfunction "TP_TP") (pintype "input"))
      (node (ref "U1") (pin "P$3") (pinfunction "EN_P$3") (pintype "bidirectional"))
    )
    (net (code "27") (name "/IN1_SOLE") (class "Default")
      (node (ref "U1") (pin "P$24") (pinfunction "GPIO2_P$24") (pintype "bidirectional"))
      (node (ref "U9") (pin "5") (pinfunction "IN1H_5") (pintype "bidirectional"))
      (node (ref "U9") (pin "8") (pinfunction "IN2L_8") (pintype "bidirectional"))
    )
    (net (code "28") (name "/IN2_SOLE") (class "Default")
      (node (ref "U1") (pin "P$23") (pinfunction "GPIO15_P$23") (pintype "bidirectional"))
      (node (ref "U9") (pin "6") (pinfunction "IN1L_6") (pintype "bidirectional"))
      (node (ref "U9") (pin "7") (pinfunction "IN2H_7") (pintype "bidirectional"))
    )
    (net (code "29") (name "/IO0") (class "Default")
      (node (ref "R29") (pin "1") (pinfunction "1_1") (pintype "passive"))
      (node (ref "R30") (pin "2") (pinfunction "2_2") (pintype "passive"))
      (node (ref "T1") (pin "6") (pinfunction "C_6") (pintype "passive"))
      (node (ref "TP20") (pin "TP") (pinfunction "TP_TP") (pintype "input"))
      (node (ref "U1") (pin "P$25") (pinfunction "GPIO0_P$25") (pintype "bidirectional"))
    )
    (net (code "30") (name "/MODE0") (class "Default")
      (node (ref "JP2") (pin "P$1") (pinfunction "P$1_P$1") (pintype "bidirectional"))
      (node (ref "JP8") (pin "P$2") (pinfunction "P$2_P$2") (pintype "bidirectional"))
      (node (ref "JP9") (pin "P$1") (pinfunction "P$1_P$1") (pintype "bidirectional"))
      (node (ref "U6") (pin "13") (pinfunction "M0_13") (pintype "bidirectional"))
      (node (ref "U7") (pin "13") (pinfunction "M0_13") (pintype "bidirectional"))
      (node (ref "U8") (pin "13") (pinfunction "M0_13") (pintype "bidirectional"))
    )
    (net (code "31") (name "/MODE1") (class "Default")
      (node (ref "JP1") (pin "P$1") (pinfunction "P$1_P$1") (pintype "bidirectional"))
      (node (ref "JP12") (pin "P$2") (pinfunction "P$2_P$2") (pintype "bidirectional"))
      (node (ref "JP13") (pin "P$1") (pinfunction "P$1_P$1") (pintype "bidirectional"))
      (node (ref "U6") (pin "14") (pinfunction "M1_14") (pintype "bidirectional"))
      (node (ref "U7") (pin "14") (pinfunction "M1_14") (pintype "bidirectional"))
      (node (ref "U8") (pin "14") (pinfunction "M1_14") (pintype "bidirectional"))
    )
    (net (code "32") (name "/OE") (class "Default")
      (node (ref "U1") (pin "P$12") (pinfunction "GPIO27_P$12") (pintype "bidirectional"))
      (node (ref "U4") (pin "13") (pinfunction "OE_13") (pintype "bidirectional"))
    )
    (net (code "33") (name "/ON-OFF_PB") (class "Default")
      (node (ref "P1") (pin "P$4") (pinfunction "P$4_P$4") (pintype "bidirectional"))
      (node (ref "U2") (pin "5") (pinfunction "PB_5") (pintype "bidirectional"))
    )
    (net (code "34") (name "/OPEN_PB") (class "Default")
      (node (ref "P1") (pin "P$5") (pinfunction "P$5_P$5") (pintype "bidirectional"))
      (node (ref "R41") (pin "1") (pinfunction "1_1") (pintype "passive"))
      (node (ref "TP30") (pin "TP") (pinfunction "TP_TP") (pintype "input"))
      (node (ref "U1") (pin "P$6") (pinfunction "GPIO34_P$6") (pintype "bidirectional"))
    )
    (net (code "35") (name "/OUT1_SOLE") (class "Default")
      (node (ref "P4") (pin "P$1") (pinfunction "P$1_P$1") (pintype "bidirectional"))
      (node (ref "P4") (pin "P$2") (pinfunction "P$2_P$2") (pintype "bidirectional"))
      (node (ref "TP22") (pin "TP") (pinfunction "TP_TP") (pintype "input"))
      (node (ref "U9") (pin "2") (pinfunction "OUT1_2") (pintype "bidirectional"))
      (node (ref "U9") (pin "3") (pinfunction "OUT1_3") (pintype "bidirectional"))
      (node (ref "U9") (pin "4") (pinfunction "OUT1_4") (pintype "bidirectional"))
    )
    (net (code "36") (name "/OUT2_SOLE") (class "Default")
      (node (ref "P4") (pin "P$3") (pinfunction "P$3_P$3") (pintype "bidirectional"))
      (node (ref "P4") (pin "P$4") (pinfunction "P$4_P$4") (pintype "bidirectional"))
      (node (ref "TP23") (pin "TP") (pinfunction "TP_TP") (pintype "input"))
      (node (ref "U9") (pin "21") (pinfunction "OUT2_21") (pintype "bidirectional"))
      (node (ref "U9") (pin "22") (pinfunction "OUT2_22") (pintype "bidirectional"))
      (node (ref "U9") (pin "23") (pinfunction "OUT2_23") (pintype "bidirectional"))
    )
    (net (code "37") (name "/PWR_EN") (class "Default")
      (node (ref "U2") (pin "7") (pinfunction "EN_7") (pintype "bidirectional"))
      (node (ref "VR1") (pin "1") (pinfunction "EN_1") (pintype "bidirectional"))
    )
    (net (code "38") (name "/RTS") (class "Default")
      (node (ref "R19") (pin "1") (pinfunction "1_1") (pintype "passive"))
      (node (ref "T1") (pin "4") (pinfunction "E_4") (pintype "passive"))
      (node (ref "U5") (pin "24") (pinfunction "RTS_24") (pintype "bidirectional"))
    )
    (net (code "39") (name "/SHCP") (class "Default")
      (node (ref "U1") (pin "P$10") (pinfunction "GPIO25_P$10") (pintype "bidirectional"))
      (node (ref "U4") (pin "11") (pinfunction "SHCP_11") (pintype "bidirectional"))
    )
    (net (code "40") (name "/SLEEP_M1") (class "Default")
      (node (ref "TP8") (pin "TP") (pinfunction "TP_TP") (pintype "input"))
      (node (ref "U1") (pin "P$33") (pinfunction "GPIO21_P$33") (pintype "bidirectional"))
      (node (ref "U6") (pin "1") (pinfunction "~{SLEEP}_1") (pintype "bidirectional"))
    )
    (net (code "41") (name "/SLEEP_M2") (class "Default")
      (node (ref "TP11") (pin "TP") (pinfunction "TP_TP") (pintype "input"))
      (node (ref "U1") (pin "P$29") (pinfunction "GPIO5_P$29") (pintype "bidirectional"))
      (node (ref "U8") (pin "1") (pinfunction "~{SLEEP}_1") (pintype "bidirectional"))
    )
    (net (code "42") (name "/SLEEP_M3") (class "Default")
      (node (ref "TP14") (pin "TP") (pinfunction "TP_TP") (pintype "input"))
      (node (ref "U1") (pin "P$26") (pinfunction "GPIO4_P$26") (pintype "bidirectional"))
      (node (ref "U7") (pin "1") (pinfunction "~{SLEEP}_1") (pintype "bidirectional"))
    )
    (net (code "43") (name "/SLEEP_SOLE") (class "Default")
      (node (ref "R31") (pin "2") (pinfunction "2_2") (pintype "passive"))
      (node (ref "U1") (pin "P$16") (pinfunction "GPIO13_P$16") (pintype "bidirectional"))
      (node (ref "U9") (pin "9") (pinfunction "~{SLEEP}_9") (pintype "bidirectional"))
    )
    (net (code "44") (name "/STATE_LED_B") (class "Default")
      (node (ref "P1") (pin "P$9") (pinfunction "P$9_P$9") (pintype "bidirectional"))
      (node (ref "U4") (pin "2") (pinfunction "Q2_2") (pintype "bidirectional"))
    )
    (net (code "45") (name "/STATE_LED_G") (class "Default")
      (node (ref "P1") (pin "P$8") (pinfunction "P$8_P$8") (pintype "bidirectional"))
      (node (ref "U4") (pin "1") (pinfunction "Q1_1") (pintype "bidirectional"))
    )
    (net (code "46") (name "/STATE_LED_R") (class "Default")
      (node (ref "P1") (pin "P$7") (pinfunction "P$7_P$7") (pintype "bidirectional"))
      (node (ref "U4") (pin "15") (pinfunction "Q0_15") (pintype "bidirectional"))
    )
    (net (code "47") (name "/STCP") (class "Default")
      (node (ref "U1") (pin "P$11") (pinfunction "GPIO26_P$11") (pintype "bidirectional"))
      (node (ref "U4") (pin "12") (pinfunction "STCP_12") (pintype "bidirectional"))
    )
    (net (code "48") (name "/STEP_M1") (class "Default")
      (node (ref "TP6") (pin "TP") (pinfunction "TP_TP") (pintype "input"))
      (node (ref "U1") (pin "P$37") (pinfunction "GPIO23_P$37") (pintype "bidirectional"))
      (node (ref "U6") (pin "11") (pinfunction "STEP_11") (pintype "bidirectional"))
    )
    (net (code "49") (name "/STEP_M2") (class "Default")
      (node (ref "TP9") (pin "TP") (pinfunction "TP_TP") (pintype "input"))
      (node (ref "U1") (pin "P$31") (pinfunction "GPIO19_P$31") (pintype "bidirectional"))
      (node (ref "U8") (pin "11") (pinfunction "STEP_11") (pintype "bidirectional"))
    )
    (net (code "50") (name "/STEP_M3") (class "Default")
      (node (ref "TP12") (pin "TP") (pinfunction "TP_TP") (pintype "input"))
      (node (ref "U1") (pin "P$28") (pinfunction "GPIO17_P$28") (pintype "bidirectional"))
      (node (ref "U7") (pin "11") (pinfunction "STEP_11") (pintype "bidirectional"))
    )
    (net (code "51") (name "/U0RX") (class "Default")
      (node (ref "JP3") (pin "P$2") (pinfunction "P$2_P$2") (pintype "bidirectional"))
      (node (ref "TP17") (pin "TP") (pinfunction "TP_TP") (pintype "input"))
      (node (ref "U1") (pin "P$34") (pinfunction "RXD0_P$34") (pintype "bidirectional"))
    )
    (net (code "52") (name "/U0TX") (class "Default")
      (node (ref "JP4") (pin "P$2") (pinfunction "P$2_P$2") (pintype "bidirectional"))
      (node (ref "TP18") (pin "TP") (pinfunction "TP_TP") (pintype "input"))
      (node (ref "U1") (pin "P$35") (pinfunction "TXD0_P$35") (pintype "bidirectional"))
    )
    (net (code "53") (name "/VBAT") (class "Default")
      (node (ref "C3") (pin "1") (pinfunction "1_1") (pintype "passive"))
      (node (ref "C6") (pin "1") (pinfunction "1_1") (pintype "passive"))
      (node (ref "J1") (pin "1") (pinfunction "1_1") (pintype "bidirectional"))
      (node (ref "JP11") (pin "P$2") (pinfunction "P$2_P$2") (pintype "bidirectional"))
      (node (ref "JP5") (pin "P$2") (pinfunction "P$2_P$2") (pintype "bidirectional"))
      (node (ref "R36") (pin "1") (pinfunction "1_1") (pintype "passive"))
      (node (ref "TP28") (pin "TP") (pinfunction "TP_TP") (pintype "input"))
      (node (ref "U2") (pin "6") (pinfunction "VIN_6") (pintype "bidirectional"))
      (node (ref "U3") (pin "3") (pinfunction "BAT_3") (pintype "bidirectional"))
      (node (ref "VR1") (pin "2") (pinfunction "IN_2") (pintype "bidirectional"))
    )
    (net (code "54") (name "/VMOT") (class "Default")
      (node (ref "C14") (pin "1") (pinfunction "1_1") (pintype "passive"))
      (node (ref "C15") (pin "1") (pinfunction "1_1") (pintype "passive"))
      (node (ref "C16") (pin "1") (pinfunction "1_1") (pintype "passive"))
      (node (ref "C17") (pin "1") (pinfunction "1_1") (pintype "passive"))
      (node (ref "C18") (pin "1") (pinfunction "1_1") (pintype "passive"))
      (node (ref "C19") (pin "1") (pinfunction "1_1") (pintype "passive"))
      (node (ref "C20") (pin "1") (pinfunction "1_1") (pintype "passive"))
      (node (ref "C21") (pin "1") (pinfunction "1_1") (pintype "passive"))
      (node (ref "C28") (pin "1") (pinfunction "1_1") (pintype "passive"))
      (node (ref "C29") (pin "1") (pinfunction "1_1") (pintype "passive"))
      (node (ref "C31") (pin "1") (pinfunction "1_1") (pintype "passive"))
      (node (ref "C32") (pin "1") (pinfunction "1_1") (pintype "passive"))
      (node (ref "JP10") (pin "P$2") (pinfunction "P$2_P$2") (pintype "bidirectional"))
      (node (ref "JP11") (pin "P$1") (pinfunction "P$1_P$1") (pintype "bidirectional"))
      (node (ref "U6") (pin "18") (pinfunction "VMOT_18") (pintype "bidirectional"))
      (node (ref "U6") (pin "19") (pinfunction "VMOT_19") (pintype "bidirectional"))
      (node (ref "U7") (pin "18") (pinfunction "VMOT_18") (pintype "bidirectional"))
      (node (ref "U7") (pin "19") (pinfunction "VMOT_19") (pintype "bidirectional"))
      (node (ref "U8") (pin "18") (pinfunction "VMOT_18") (pintype "bidirectional"))
      (node (ref "U8") (pin "19") (pinfunction "VMOT_19") (pintype "bidirectional"))
    )
    (net (code "55") (name "/VUSB") (class "Default")
      (node (ref "C11") (pin "1") (pinfunction "1_1") (pintype "passive"))
      (node (ref "C5") (pin "1") (pinfunction "1_1") (pintype "passive"))
      (node (ref "P1") (pin "P$1") (pinfunction "P$1_P$1") (pintype "bidirectional"))
      (node (ref "TP27") (pin "TP") (pinfunction "TP_TP") (pintype "input"))
      (node (ref "U3") (pin "4") (pinfunction "VCC_4") (pintype "bidirectional"))
      (node (ref "U5") (pin "7") (pinfunction "REGIN_7") (pintype "bidirectional"))
      (node (ref "U5") (pin "8") (pinfunction "VBUS_8") (pintype "bidirectional"))
    )
    (net (code "56") (name "/~{PWR_KILL}") (class "Default")
      (node (ref "R1") (pin "2") (pinfunction "2_2") (pintype "passive"))
      (node (ref "TP5") (pin "TP") (pinfunction "TP_TP") (pintype "input"))
      (node (ref "U1") (pin "P$8") (pinfunction "GPIO32_P$8") (pintype "bidirectional"))
      (node (ref "U2") (pin "2") (pinfunction "KILL_2") (pintype "bidirectional"))
    )
    (net (code "57") (name "/~{TURN_OFF}") (class "Default")
      (node (ref "R2") (pin "2") (pinfunction "2_2") (pintype "passive"))
      (node (ref "TP4") (pin "TP") (pinfunction "TP_TP") (pintype "input"))
      (node (ref "U1") (pin "P$4") (pinfunction "SENSOR_VP_P$4") (pintype "bidirectional"))
      (node (ref "U2") (pin "8") (pinfunction "INT_8") (pintype "bidirectional"))
    )
    (net (code "58") (name "GND") (class "Default")
      (node (ref "C1") (pin "2") (pinfunction "2_2") (pintype "passive"))
      (node (ref "C10") (pin "2") (pinfunction "2_2") (pintype "passive"))
      (node (ref "C11") (pin "2") (pinfunction "2_2") (pintype "passive"))
      (node (ref "C12") (pin "2") (pinfunction "2_2") (pintype "passive"))
      (node (ref "C13") (pin "2") (pinfunction "2_2") (pintype "passive"))
      (node (ref "C16") (pin "2") (pinfunction "2_2") (pintype "passive"))
      (node (ref "C17") (pin "2") (pinfunction "2_2") (pintype "passive"))
      (node (ref "C18") (pin "2") (pinfunction "2_2") (pintype "passive"))
      (node (ref "C19") (pin "2") (pinfunction "2_2") (pintype "passive"))
      (node (ref "C2") (pin "2") (pinfunction "2_2") (pintype "passive"))
      (node (ref "C20") (pin "2") (pinfunction "2_2") (pintype "passive"))
      (node (ref "C21") (pin "2") (pinfunction "2_2") (pintype "passive"))
      (node (ref "C22") (pin "2") (pinfunction "2_2") (pintype "passive"))
      (node (ref "C23") (pin "1") (pinfunction "1_1") (pintype "passive"))
      (node (ref "C24") (pin "1") (pinfunction "1_1") (pintype "passive"))
      (node (ref "C25") (pin "1") (pinfunction "1_1") (pintype "passive"))
      (node (ref "C26") (pin "1") (pinfunction "1_1") (pintype "passive"))
      (node (ref "C27") (pin "2") (pinfunction "2_2") (pintype "passive"))
      (node (ref "C29") (pin "2") (pinfunction "2_2") (pintype "passive"))
      (node (ref "C3") (pin "2") (pinfunction "2_2") (pintype "passive"))
      (node (ref "C31") (pin "2") (pinfunction "2_2") (pintype "passive"))
      (node (ref "C32") (pin "2") (pinfunction "2_2") (pintype "passive"))
      (node (ref "C4") (pin "2") (pinfunction "2_2") (pintype "passive"))
      (node (ref "C5") (pin "2") (pinfunction "2_2") (pintype "passive"))
      (node (ref "C6") (pin "2") (pinfunction "2_2") (pintype "passive"))
      (node (ref "C7") (pin "2") (pinfunction "2_2") (pintype "passive"))
      (node (ref "C8") (pin "1") (pinfunction "1_1") (pintype "passive"))
      (node (ref "C9") (pin "1") (pinfunction "1_1") (pintype "passive"))
      (node (ref "J1") (pin "2") (pinfunction "2_2") (pintype "bidirectional"))
      (node (ref "JP13") (pin "P$2") (pinfunction "P$2_P$2") (pintype "bidirectional"))
      (node (ref "JP9") (pin "P$2") (pinfunction "P$2_P$2") (pintype "bidirectional"))
      (node (ref "P1") (pin "P$13") (pinfunction "P$13_P$13") (pintype "bidirectional"))
      (node (ref "P1") (pin "P$14") (pinfunction "P$14_P$14") (pintype "bidirectional"))
      (node (ref "R10") (pin "1") (pinfunction "1_1") (pintype "passive"))
      (node (ref "R11") (pin "1") (pinfunction "1_1") (pintype "passive"))
      (node (ref "R12") (pin "1") (pinfunction "1_1") (pintype "passive"))
      (node (ref "R13") (pin "1") (pinfunction "1_1") (pintype "passive"))
      (node (ref "R14") (pin "1") (pinfunction "1_1") (pintype "passive"))
      (node (ref "R15") (pin "1") (pinfunction "1_1") (pintype "passive"))
      (node (ref "R16") (pin "1") (pinfunction "1_1") (pintype "passive"))
      (node (ref "R17") (pin "1") (pinfunction "1_1") (pintype "passive"))
      (node (ref "R21") (pin "1") (pinfunction "1_1") (pintype "passive"))
      (node (ref "R3") (pin "1") (pinfunction "1_1") (pintype "passive"))
      (node (ref "R31") (pin "1") (pinfunction "1_1") (pintype "passive"))
      (node (ref "R32") (pin "1") (pinfunction "1_1") (pintype "passive"))
      (node (ref "R33") (pin "1") (pinfunction "1_1") (pintype "passive"))
      (node (ref "R34") (pin "1") (pinfunction "1_1") (pintype "passive"))
      (node (ref "R35") (pin "1") (pinfunction "1_1") (pintype "passive"))
      (node (ref "R37") (pin "2") (pinfunction "2_2") (pintype "passive"))
      (node (ref "R38") (pin "1") (pinfunction "1_1") (pintype "passive"))
      (node (ref "R39") (pin "1") (pinfunction "1_1") (pintype "passive"))
      (node (ref "R40") (pin "1") (pinfunction "1_1") (pintype "passive"))
      (node (ref "R5") (pin "1") (pinfunction "1_1") (pintype "passive"))
      (node (ref "R7") (pin "1") (pinfunction "1_1") (pintype "passive"))
      (node (ref "S1") (pin "P$1") (pinfunction "P_P$1") (pintype "passive"))
      (node (ref "S2") (pin "P$1") (pinfunction "P_P$1") (pintype "passive"))
      (node (ref "TP29") (pin "TP") (pinfunction "TP_TP") (pintype "input"))
      (node (ref "U1") (pin "P$1") (pinfunction "GND_P$1") (pintype "bidirectional"))
      (node (ref "U1") (pin "P$15") (pinfunction "GND_P$15") (pintype "bidirectional"))
      (node (ref "U1") (pin "P$38") (pinfunction "GND_P$38") (pintype "bidirectional"))
      (node (ref "U1") (pin "P$40") (pinfunction "PAD_P$40") (pintype "bidirectional"))
      (node (ref "U2") (pin "1") (pinfunction "ON_1") (pintype "bidirectional"))
      (node (ref "U2") (pin "4") (pinfunction "GND_4") (pintype "bidirectional"))
      (node (ref "U3") (pin "2") (pinfunction "GND_2") (pintype "bidirectional"))
      (node (ref "U4") (pin "8") (pinfunction "GND_8") (pintype "bidirectional"))
      (node (ref "U5") (pin "29") (pinfunction "GND_PAD_29") (pintype "bidirectional"))
      (node (ref "U5") (pin "3") (pinfunction "GND_3") (pintype "bidirectional"))
      (node (ref "U6") (pin "21") (pinfunction "GND_21") (pintype "bidirectional"))
      (node (ref "U6") (pin "25") (pinfunction "GND_PAD_25") (pintype "bidirectional"))
      (node (ref "U7") (pin "21") (pinfunction "GND_21") (pintype "bidirectional"))
      (node (ref "U7") (pin "25") (pinfunction "GND_PAD_25") (pintype "bidirectional"))
      (node (ref "U8") (pin "21") (pinfunction "GND_21") (pintype "bidirectional"))
      (node (ref "U8") (pin "25") (pinfunction "GND_PAD_25") (pintype "bidirectional"))
      (node (ref "U9") (pin "1") (pinfunction "GND_1") (pintype "bidirectional"))
      (node (ref "U9") (pin "12") (pinfunction "GND_12") (pintype "bidirectional"))
      (node (ref "U9") (pin "13") (pinfunction "GND_13") (pintype "bidirectional"))
      (node (ref "U9") (pin "24") (pinfunction "GND_24") (pintype "bidirectional"))
      (node (ref "U9") (pin "25") (pinfunction "GND_25") (pintype "bidirectional"))
      (node (ref "VR1") (pin "3") (pinfunction "GND_3") (pintype "bidirectional"))
      (node (ref "VR1") (pin "6") (pinfunction "GND_6") (pintype "bidirectional"))
    )
    (net (code "59") (name "Net-(C23-Pad2)") (class "Default")
      (node (ref "C23") (pin "2") (pinfunction "2_2") (pintype "passive"))
      (node (ref "C24") (pin "2") (pinfunction "2_2") (pintype "passive"))
      (node (ref "C25") (pin "2") (pinfunction "2_2") (pintype "passive"))
      (node (ref "C26") (pin "2") (pinfunction "2_2") (pintype "passive"))
      (node (ref "C30") (pin "1") (pinfunction "1_1") (pintype "passive"))
      (node (ref "JP7") (pin "P$2") (pinfunction "P$2_P$2") (pintype "bidirectional"))
      (node (ref "R23") (pin "2") (pinfunction "2_2") (pintype "passive"))
      (node (ref "R24") (pin "2") (pinfunction "2_2") (pintype "passive"))
      (node (ref "R25") (pin "2") (pinfunction "2_2") (pintype "passive"))
      (node (ref "R26") (pin "2") (pinfunction "2_2") (pintype "passive"))
      (node (ref "U9") (pin "18") (pinfunction "VCC_18") (pintype "bidirectional"))
      (node (ref "U9") (pin "19") (pinfunction "VCC_19") (pintype "bidirectional"))
      (node (ref "U9") (pin "20") (pinfunction "VCC_20") (pintype "bidirectional"))
    )
    (net (code "60") (name "Net-(JP5-PadP$1)") (class "Default")
      (node (ref "JP5") (pin "P$1") (pinfunction "P$1_P$1") (pintype "bidirectional"))
      (node (ref "JP6") (pin "P$1") (pinfunction "P$1_P$1") (pintype "bidirectional"))
      (node (ref "JP7") (pin "P$1") (pinfunction "P$1_P$1") (pintype "bidirectional"))
      (node (ref "R23") (pin "1") (pinfunction "1_1") (pintype "passive"))
      (node (ref "R24") (pin "1") (pinfunction "1_1") (pintype "passive"))
      (node (ref "R25") (pin "1") (pinfunction "1_1") (pintype "passive"))
      (node (ref "R26") (pin "1") (pinfunction "1_1") (pintype "passive"))
    )
    (net (code "61") (name "Net-(S1-S)") (class "Default")
      (node (ref "R28") (pin "1") (pinfunction "1_1") (pintype "passive"))
      (node (ref "S1") (pin "P$2") (pinfunction "S_P$2") (pintype "passive"))
    )
    (net (code "62") (name "Net-(S2-S)") (class "Default")
      (node (ref "R30") (pin "1") (pinfunction "1_1") (pintype "passive"))
      (node (ref "S2") (pin "P$2") (pinfunction "S_P$2") (pintype "passive"))
    )
    (net (code "63") (name "Net-(T1A-B)") (class "Default")
      (node (ref "R18") (pin "2") (pinfunction "2_2") (pintype "passive"))
      (node (ref "T1") (pin "5") (pinfunction "B_5") (pintype "passive"))
    )
    (net (code "64") (name "Net-(T1B-B)") (class "Default")
      (node (ref "R19") (pin "2") (pinfunction "2_2") (pintype "passive"))
      (node (ref "T1") (pin "2") (pinfunction "B_2") (pintype "passive"))
    )
    (net (code "65") (name "Net-(U1-GPIO12)") (class "Default")
      (node (ref "JP2") (pin "P$2") (pinfunction "P$2_P$2") (pintype "bidirectional"))
      (node (ref "TP1") (pin "TP") (pinfunction "TP_TP") (pintype "input"))
      (node (ref "U1") (pin "P$14") (pinfunction "GPIO12_P$14") (pintype "bidirectional"))
    )
    (net (code "66") (name "Net-(U1-GPIO14)") (class "Default")
      (node (ref "JP1") (pin "P$2") (pinfunction "P$2_P$2") (pintype "bidirectional"))
      (node (ref "TP3") (pin "TP") (pinfunction "TP_TP") (pintype "input"))
      (node (ref "U1") (pin "P$13") (pinfunction "GPIO14_P$13") (pintype "bidirectional"))
    )
    (net (code "67") (name "Net-(U1-GPIO35)") (class "Default")
      (node (ref "TP2") (pin "TP") (pinfunction "TP_TP") (pintype "input"))
      (node (ref "U1") (pin "P$7") (pinfunction "GPIO35_P$7") (pintype "bidirectional"))
    )
    (net (code "68") (name "Net-(U2-TMR)") (class "Default")
      (node (ref "C7") (pin "1") (pinfunction "1_1") (pintype "passive"))
      (node (ref "U2") (pin "3") (pinfunction "TMR_3") (pintype "bidirectional"))
    )
    (net (code "69") (name "Net-(U3-PROG)") (class "Default")
      (node (ref "R3") (pin "2") (pinfunction "2_2") (pintype "passive"))
      (node (ref "U3") (pin "5") (pinfunction "PROG_5") (pintype "bidirectional"))
    )
    (net (code "70") (name "Net-(U5-RXD)") (class "Default")
      (node (ref "JP4") (pin "P$1") (pinfunction "P$1_P$1") (pintype "bidirectional"))
      (node (ref "U5") (pin "25") (pinfunction "RXD_25") (pintype "bidirectional"))
    )
    (net (code "71") (name "Net-(U5-TXD)") (class "Default")
      (node (ref "JP3") (pin "P$1") (pinfunction "P$1_P$1") (pintype "bidirectional"))
      (node (ref "U5") (pin "26") (pinfunction "TXD_26") (pintype "bidirectional"))
    )
    (net (code "72") (name "Net-(U5-VDD)") (class "Default")
      (node (ref "C10") (pin "1") (pinfunction "1_1") (pintype "passive"))
      (node (ref "U5") (pin "6") (pinfunction "VDD_6") (pintype "bidirectional"))
    )
    (net (code "73") (name "Net-(U6-ADECAY)") (class "Default")
      (node (ref "R12") (pin "2") (pinfunction "2_2") (pintype "passive"))
      (node (ref "U6") (pin "3") (pinfunction "ADECAY_3") (pintype "bidirectional"))
    )
    (net (code "74") (name "Net-(U6-AISEN)") (class "Default")
      (node (ref "R16") (pin "2") (pinfunction "2_2") (pintype "passive"))
      (node (ref "U6") (pin "5") (pinfunction "AISEN_5") (pintype "bidirectional"))
    )
    (net (code "75") (name "Net-(U6-AVREF)") (class "Default")
      (node (ref "R4") (pin "1") (pinfunction "1_1") (pintype "passive"))
      (node (ref "R5") (pin "2") (pinfunction "2_2") (pintype "passive"))
      (node (ref "U6") (pin "22") (pinfunction "AVREF_22") (pintype "bidirectional"))
      (node (ref "U6") (pin "23") (pinfunction "BVREF_23") (pintype "bidirectional"))
    )
    (net (code "76") (name "Net-(U6-BDECAY)") (class "Default")
      (node (ref "R10") (pin "2") (pinfunction "2_2") (pintype "passive"))
      (node (ref "U6") (pin "2") (pinfunction "BDECAY_2") (pintype "bidirectional"))
    )
    (net (code "77") (name "Net-(U6-BISEN)") (class "Default")
      (node (ref "R14") (pin "2") (pinfunction "2_2") (pintype "passive"))
      (node (ref "U6") (pin "8") (pinfunction "BISEN_8") (pintype "bidirectional"))
    )
    (net (code "78") (name "Net-(U6-CONFIG)") (class "Default")
      (node (ref "R8") (pin "2") (pinfunction "2_2") (pintype "passive"))
      (node (ref "U6") (pin "15") (pinfunction "CONFIG_15") (pintype "bidirectional"))
    )
    (net (code "79") (name "Net-(U6-VCP)") (class "Default")
      (node (ref "C14") (pin "2") (pinfunction "2_2") (pintype "passive"))
      (node (ref "U6") (pin "17") (pinfunction "VCP_17") (pintype "bidirectional"))
    )
    (net (code "80") (name "Net-(U6-VINT)") (class "Default")
      (node (ref "C12") (pin "1") (pinfunction "1_1") (pintype "passive"))
      (node (ref "U6") (pin "20") (pinfunction "VINT_20") (pintype "bidirectional"))
    )
    (net (code "81") (name "Net-(U6-VREFO)") (class "Default")
      (node (ref "R4") (pin "2") (pinfunction "2_2") (pintype "passive"))
      (node (ref "U6") (pin "24") (pinfunction "VREFO_24") (pintype "bidirectional"))
    )
    (net (code "82") (name "Net-(U6-~{FAULT})") (class "Default")
      (node (ref "TP15") (pin "TP") (pinfunction "TP_TP") (pintype "input"))
      (node (ref "U6") (pin "16") (pinfunction "~{FAULT}_16") (pintype "bidirectional"))
    )
    (net (code "83") (name "Net-(U7-ADECAY)") (class "Default")
      (node (ref "R13") (pin "2") (pinfunction "2_2") (pintype "passive"))
      (node (ref "U7") (pin "3") (pinfunction "ADECAY_3") (pintype "bidirectional"))
    )
    (net (code "84") (name "Net-(U7-AISEN)") (class "Default")
      (node (ref "R17") (pin "2") (pinfunction "2_2") (pintype "passive"))
      (node (ref "U7") (pin "5") (pinfunction "AISEN_5") (pintype "bidirectional"))
    )
    (net (code "85") (name "Net-(U7-AVREF)") (class "Default")
      (node (ref "R6") (pin "1") (pinfunction "1_1") (pintype "passive"))
      (node (ref "R7") (pin "2") (pinfunction "2_2") (pintype "passive"))
      (node (ref "U7") (pin "22") (pinfunction "AVREF_22") (pintype "bidirectional"))
      (node (ref "U7") (pin "23") (pinfunction "BVREF_23") (pintype "bidirectional"))
    )
    (net (code "86") (name "Net-(U7-BDECAY)") (class "Default")
      (node (ref "R11") (pin "2") (pinfunction "2_2") (pintype "passive"))
      (node (ref "U7") (pin "2") (pinfunction "BDECAY_2") (pintype "bidirectional"))
    )
    (net (code "87") (name "Net-(U7-BISEN)") (class "Default")
      (node (ref "R15") (pin "2") (pinfunction "2_2") (pintype "passive"))
      (node (ref "U7") (pin "8") (pinfunction "BISEN_8") (pintype "bidirectional"))
    )
    (net (code "88") (name "Net-(U7-CONFIG)") (class "Default")
      (node (ref "R9") (pin "2") (pinfunction "2_2") (pintype "passive"))
      (node (ref "U7") (pin "15") (pinfunction "CONFIG_15") (pintype "bidirectional"))
    )
    (net (code "89") (name "Net-(U7-VCP)") (class "Default")
      (node (ref "C15") (pin "2") (pinfunction "2_2") (pintype "passive"))
      (node (ref "U7") (pin "17") (pinfunction "VCP_17") (pintype "bidirectional"))
    )
    (net (code "90") (name "Net-(U7-VINT)") (class "Default")
      (node (ref "C13") (pin "1") (pinfunction "1_1") (pintype "passive"))
      (node (ref "U7") (pin "20") (pinfunction "VINT_20") (pintype "bidirectional"))
    )
    (net (code "91") (name "Net-(U7-VREFO)") (class "Default")
      (node (ref "R6") (pin "2") (pinfunction "2_2") (pintype "passive"))
      (node (ref "U7") (pin "24") (pinfunction "VREFO_24") (pintype "bidirectional"))
    )
    (net (code "92") (name "Net-(U7-~{FAULT})") (class "Default")
      (node (ref "TP16") (pin "TP") (pinfunction "TP_TP") (pintype "input"))
      (node (ref "U7") (pin "16") (pinfunction "~{FAULT}_16") (pintype "bidirectional"))
    )
    (net (code "93") (name "Net-(U8-ADECAY)") (class "Default")
      (node (ref "R34") (pin "2") (pinfunction "2_2") (pintype "passive"))
      (node (ref "U8") (pin "3") (pinfunction "ADECAY_3") (pintype "bidirectional"))
    )
    (net (code "94") (name "Net-(U8-AISEN)") (class "Default")
      (node (ref "R38") (pin "2") (pinfunction "2_2") (pintype "passive"))
      (node (ref "U8") (pin "5") (pinfunction "AISEN_5") (pintype "bidirectional"))
    )
    (net (code "95") (name "Net-(U8-AVREF)") (class "Default")
      (node (ref "R20") (pin "1") (pinfunction "1_1") (pintype "passive"))
      (node (ref "R21") (pin "2") (pinfunction "2_2") (pintype "passive"))
      (node (ref "U8") (pin "22") (pinfunction "AVREF_22") (pintype "bidirectional"))
      (node (ref "U8") (pin "23") (pinfunction "BVREF_23") (pintype "bidirectional"))
    )
    (net (code "96") (name "Net-(U8-BDECAY)") (class "Default")
      (node (ref "R33") (pin "2") (pinfunction "2_2") (pintype "passive"))
      (node (ref "U8") (pin "2") (pinfunction "BDECAY_2") (pintype "bidirectional"))
    )
    (net (code "97") (name "Net-(U8-BISEN)") (class "Default")
      (node (ref "R35") (pin "2") (pinfunction "2_2") (pintype "passive"))
      (node (ref "U8") (pin "8") (pinfunction "BISEN_8") (pintype "bidirectional"))
    )
    (net (code "98") (name "Net-(U8-CONFIG)") (class "Default")
      (node (ref "R22") (pin "2") (pinfunction "2_2") (pintype "passive"))
      (node (ref "U8") (pin "15") (pinfunction "CONFIG_15") (pintype "bidirectional"))
    )
    (net (code "99") (name "Net-(U8-VCP)") (class "Default")
      (node (ref "C28") (pin "2") (pinfunction "2_2") (pintype "passive"))
      (node (ref "U8") (pin "17") (pinfunction "VCP_17") (pintype "bidirectional"))
    )
    (net (code "100") (name "Net-(U8-VINT)") (class "Default")
      (node (ref "C27") (pin "1") (pinfunction "1_1") (pintype "passive"))
      (node (ref "U8") (pin "20") (pinfunction "VINT_20") (pintype "bidirectional"))
    )
    (net (code "101") (name "Net-(U8-VREFO)") (class "Default")
      (node (ref "R20") (pin "2") (pinfunction "2_2") (pintype "passive"))
      (node (ref "U8") (pin "24") (pinfunction "VREFO_24") (pintype "bidirectional"))
    )
    (net (code "102") (name "Net-(U8-~{FAULT})") (class "Default")
      (node (ref "TP21") (pin "TP") (pinfunction "TP_TP") (pintype "input"))
      (node (ref "U8") (pin "16") (pinfunction "~{FAULT}_16") (pintype "bidirectional"))
    )
    (net (code "103") (name "Net-(U9-LDOEN)") (class "Default")
      (node (ref "R40") (pin "2") (pinfunction "2_2") (pintype "passive"))
      (node (ref "U9") (pin "10") (pinfunction "LDOEN_10") (pintype "bidirectional"))
    )
    (net (code "104") (name "Net-(U9-SR)") (class "Default")
      (node (ref "R32") (pin "2") (pinfunction "2_2") (pintype "passive"))
      (node (ref "U9") (pin "11") (pinfunction "SR_11") (pintype "bidirectional"))
    )
    (net (code "105") (name "Net-(U9-VCP)") (class "Default")
      (node (ref "C30") (pin "2") (pinfunction "2_2") (pintype "passive"))
      (node (ref "U9") (pin "17") (pinfunction "VCP_17") (pintype "bidirectional"))
    )
    (net (code "106") (name "Net-(U9-VPROPI)") (class "Default")
      (node (ref "R39") (pin "2") (pinfunction "2_2") (pintype "passive"))
      (node (ref "U9") (pin "16") (pinfunction "VPROPI_16") (pintype "bidirectional"))
    )
    (net (code "107") (name "unconnected-(U1-CLK-PadP$20)") (class "Default")
      (node (ref "U1") (pin "P$20") (pinfunction "CLK_P$20") (pintype "bidirectional"))
    )
    (net (code "108") (name "unconnected-(U1-CMD-PadP$19)") (class "Default")
      (node (ref "U1") (pin "P$19") (pinfunction "CMD_P$19") (pintype "bidirectional"))
    )
    (net (code "109") (name "unconnected-(U1-NC-PadP$32)") (class "Default")
      (node (ref "U1") (pin "P$32") (pinfunction "NC_P$32") (pintype "bidirectional"))
    )
    (net (code "110") (name "unconnected-(U1-SD0-PadP$21)") (class "Default")
      (node (ref "U1") (pin "P$21") (pinfunction "SD0_P$21") (pintype "bidirectional"))
    )
    (net (code "111") (name "unconnected-(U1-SD1-PadP$22)") (class "Default")
      (node (ref "U1") (pin "P$22") (pinfunction "SD1_P$22") (pintype "bidirectional"))
    )
    (net (code "112") (name "unconnected-(U1-SD2-PadP$17)") (class "Default")
      (node (ref "U1") (pin "P$17") (pinfunction "SD2_P$17") (pintype "bidirectional"))
    )
    (net (code "113") (name "unconnected-(U1-SD3-PadP$18)") (class "Default")
      (node (ref "U1") (pin "P$18") (pinfunction "SD3_P$18") (pintype "bidirectional"))
    )
    (net (code "114") (name "unconnected-(U4-Q6-Pad6)") (class "Default")
      (node (ref "U4") (pin "6") (pinfunction "Q6_6") (pintype "bidirectional"))
    )
    (net (code "115") (name "unconnected-(U4-Q7-Pad7)") (class "Default")
      (node (ref "U4") (pin "7") (pinfunction "Q7_7") (pintype "bidirectional"))
    )
    (net (code "116") (name "unconnected-(U4-Q7S-Pad9)") (class "Default")
      (node (ref "U4") (pin "9") (pinfunction "Q7S_9") (pintype "bidirectional"))
    )
    (net (code "117") (name "unconnected-(U5-CTS-Pad23)") (class "Default")
      (node (ref "U5") (pin "23") (pinfunction "CTS_23") (pintype "bidirectional"))
    )
    (net (code "118") (name "unconnected-(U5-DCD-Pad1)") (class "Default")
      (node (ref "U5") (pin "1") (pinfunction "DCD_1") (pintype "bidirectional"))
    )
    (net (code "119") (name "unconnected-(U5-DSR-Pad27)") (class "Default")
      (node (ref "U5") (pin "27") (pinfunction "DSR_27") (pintype "bidirectional"))
    )
    (net (code "120") (name "unconnected-(U5-NC-Pad10)") (class "Default")
      (node (ref "U5") (pin "10") (pinfunction "NC_10") (pintype "bidirectional"))
    )
    (net (code "121") (name "unconnected-(U5-NC-Pad13)") (class "Default")
      (node (ref "U5") (pin "13") (pinfunction "NC_13") (pintype "bidirectional"))
    )
    (net (code "122") (name "unconnected-(U5-NC-Pad14)") (class "Default")
      (node (ref "U5") (pin "14") (pinfunction "NC_14") (pintype "bidirectional"))
    )
    (net (code "123") (name "unconnected-(U5-NC-Pad15)") (class "Default")
      (node (ref "U5") (pin "15") (pinfunction "NC_15") (pintype "bidirectional"))
    )
    (net (code "124") (name "unconnected-(U5-NC-Pad16)") (class "Default")
      (node (ref "U5") (pin "16") (pinfunction "NC_16") (pintype "bidirectional"))
    )
    (net (code "125") (name "unconnected-(U5-NC-Pad17)") (class "Default")
      (node (ref "U5") (pin "17") (pinfunction "NC_17") (pintype "bidirectional"))
    )
    (net (code "126") (name "unconnected-(U5-NC-Pad18)") (class "Default")
      (node (ref "U5") (pin "18") (pinfunction "NC_18") (pintype "bidirectional"))
    )
    (net (code "127") (name "unconnected-(U5-NC-Pad19)") (class "Default")
      (node (ref "U5") (pin "19") (pinfunction "NC_19") (pintype "bidirectional"))
    )
    (net (code "128") (name "unconnected-(U5-NC-Pad20)") (class "Default")
      (node (ref "U5") (pin "20") (pinfunction "NC_20") (pintype "bidirectional"))
    )
    (net (code "129") (name "unconnected-(U5-NC-Pad21)") (class "Default")
      (node (ref "U5") (pin "21") (pinfunction "NC_21") (pintype "bidirectional"))
    )
    (net (code "130") (name "unconnected-(U5-NC-Pad22)") (class "Default")
      (node (ref "U5") (pin "22") (pinfunction "NC_22") (pintype "bidirectional"))
    )
    (net (code "131") (name "unconnected-(U5-RI-Pad2)") (class "Default")
      (node (ref "U5") (pin "2") (pinfunction "RI_2") (pintype "bidirectional"))
    )
    (net (code "132") (name "unconnected-(U5-SUSPEND-Pad12)") (class "Default")
      (node (ref "U5") (pin "12") (pinfunction "SUSPEND_12") (pintype "bidirectional"))
    )
    (net (code "133") (name "unconnected-(U5-~{RST}-Pad9)") (class "Default")
      (node (ref "U5") (pin "9") (pinfunction "~{RST}_9") (pintype "bidirectional"))
    )
    (net (code "134") (name "unconnected-(U5-~{SUSPEND}-Pad11)") (class "Default")
      (node (ref "U5") (pin "11") (pinfunction "~{SUSPEND}_11") (pintype "bidirectional"))
    )
    (net (code "135") (name "unconnected-(U6-~{ENABLE}-Pad10)") (class "Default")
      (node (ref "U6") (pin "10") (pinfunction "~{ENABLE}_10") (pintype "bidirectional"))
    )
    (net (code "136") (name "unconnected-(U7-~{ENABLE}-Pad10)") (class "Default")
      (node (ref "U7") (pin "10") (pinfunction "~{ENABLE}_10") (pintype "bidirectional"))
    )
    (net (code "137") (name "unconnected-(U8-~{ENABLE}-Pad10)") (class "Default")
      (node (ref "U8") (pin "10") (pinfunction "~{ENABLE}_10") (pintype "bidirectional"))
    )
    (net (code "138") (name "unconnected-(U9-LDOFB-Pad14)") (class "Default")
      (node (ref "U9") (pin "14") (pinfunction "LDOFB_14") (pintype "bidirectional"))
    )
    (net (code "139") (name "unconnected-(U9-LDOOUT-Pad15)") (class "Default")
      (node (ref "U9") (pin "15") (pinfunction "LDOOUT_15") (pintype "bidirectional"))
    )
    (net (code "140") (name "unconnected-(VR1-NC-Pad5)") (class "Default")
      (node (ref "VR1") (pin "5") (pinfunction "NC_5") (pintype "bidirectional"))
    )
  )
)
